# 03_-_LED7SEG.net
KiCad netlist of a schematic drawn in Altium Designer
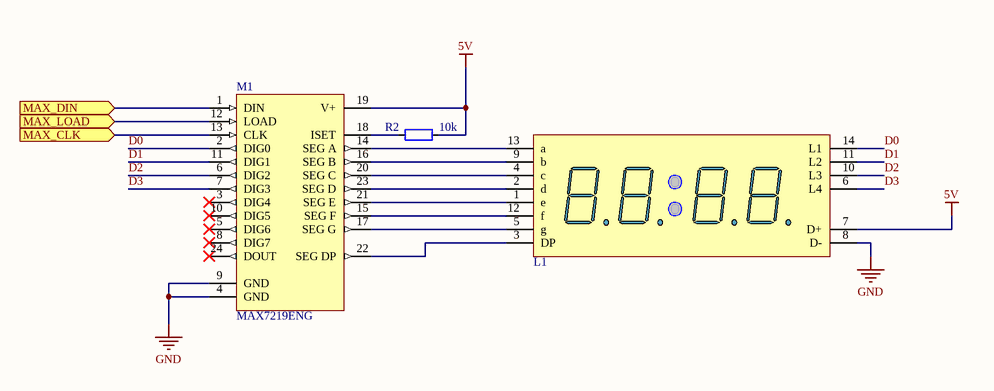
[diagram p0: [03] - LED7SEG.SchDoc]

(export (version "E")
  (design (tool "Eeschema 10.0.6"))
  (components
    (comp (ref "L1")
      (value "Led 7 Seg 4 digit - Anode")
      (footprint "LED7SEG-4-0.56-RG")
      (libsource (lib "My Library") (part "LED7SEG-4-RG"))
    )
    (comp (ref "M1")
      (value "MAX7219ENG")
      (footprint "DIP24/W0.3")
      (description "Serially Interfaced, 8-Digit LED Display Driver")
      (fields (field (name "PUBLISHER") "Altium Limited"))
      (libsource (lib "My Library") (part "MAX7219ENG"))
    )
    (comp (ref "R2")
      (value "10k")
      (footprint "RES-SMD-0805")
      (description "Resistor")
      (fields
        (field (name "MANUFACTURER") "Generic Components")
        (field (name "PUBLISHER") "Altium Hobart Technology Centre")
      )
      (libsource (lib "My Library") (part "Resistor - SMD"))
    )
  )
  (nets
    (net (code "1") (name "/D0") (class "Default")
      (node (ref "L1") (pin "14") (pinfunction "L1_14") (pintype "passive"))
      (node (ref "M1") (pin "2") (pinfunction "DIG0_2") (pintype "output"))
    )
    (net (code "2") (name "/D1") (class "Default")
      (node (ref "L1") (pin "11") (pinfunction "L2_11") (pintype "passive"))
      (node (ref "M1") (pin "11") (pinfunction "DIG1_11") (pintype "output"))
    )
    (net (code "3") (name "/D2") (class "Default")
      (node (ref "L1") (pin "10") (pinfunction "L3_10") (pintype "passive"))
      (node (ref "M1") (pin "6") (pinfunction "DIG2_6") (pintype "output"))
    )
    (net (code "4") (name "/D3") (class "Default")
      (node (ref "L1") (pin "6") (pinfunction "L4_6") (pintype "passive"))
      (node (ref "M1") (pin "7") (pinfunction "DIG3_7") (pintype "output"))
    )
    (net (code "5") (name "/MAX_CLK") (class "Default")
      (node (ref "M1") (pin "13") (pinfunction "CLK_13") (pintype "input"))
    )
    (net (code "6") (name "/MAX_DIN") (class "Default")
      (node (ref "M1") (pin "1") (pinfunction "DIN_1") (pintype "input"))
    )
    (net (code "7") (name "/MAX_LOAD") (class "Default")
      (node (ref "M1") (pin "12") (pinfunction "LOAD_12") (pintype "input"))
    )
    (net (code "8") (name "5V") (class "Default")
      (node (ref "L1") (pin "7") (pinfunction "D+_7") (pintype "passive"))
      (node (ref "M1") (pin "19") (pinfunction "V+_19") (pintype "power_in"))
      (node (ref "R2") (pin "2") (pinfunction "2_2") (pintype "passive"))
    )
    (net (code "9") (name "GND") (class "Default")
      (node (ref "L1") (pin "8") (pinfunction "D-_8") (pintype "passive"))
      (node (ref "M1") (pin "4") (pinfunction "GND_4") (pintype "power_in"))
      (node (ref "M1") (pin "9") (pinfunction "GND_9") (pintype "power_in"))
    )
    (net (code "10") (name "Net-(L1-DP)") (class "Default")
      (node (ref "L1") (pin "3") (pinfunction "DP_3") (pintype "passive"))
      (node (ref "M1") (pin "22") (pinfunction "SEG_DP_22") (pintype "output"))
    )
    (net (code "11") (name "Net-(L1-a)") (class "Default")
      (node (ref "L1") (pin "13") (pinfunction "a_13") (pintype "passive"))
      (node (ref "M1") (pin "14") (pinfunction "SEG_A_14") (pintype "output"))
    )
    (net (code "12") (name "Net-(L1-b)") (class "Default")
      (node (ref "L1") (pin "9") (pinfunction "b_9") (pintype "passive"))
      (node (ref "M1") (pin "16") (pinfunction "SEG_B_16") (pintype "output"))
    )
    (net (code "13") (name "Net-(L1-c)") (class "Default")
      (node (ref "L1") (pin "4") (pinfunction "c_4") (pintype "passive"))
      (node (ref "M1") (pin "20") (pinfunction "SEG_C_20") (pintype "output"))
    )
    (net (code "14") (name "Net-(L1-d)") (class "Default")
      (node (ref "L1") (pin "2") (pinfunction "d_2") (pintype "passive"))
      (node (ref "M1") (pin "23") (pinfunction "SEG_D_23") (pintype "output"))
    )
    (net (code "15") (name "Net-(L1-e)") (class "Default")
      (node (ref "L1") (pin "1") (pinfunction "e_1") (pintype "passive"))
      (node (ref "M1") (pin "21") (pinfunction "SEG_E_21") (pintype "output"))
    )
    (net (code "16") (name "Net-(L1-f)") (class "Default")
      (node (ref "L1") (pin "12") (pinfunction "f_12") (pintype "passive"))
      (node (ref "M1") (pin "15") (pinfunction "SEG_F_15") (pintype "output"))
    )
    (net (code "17") (name "Net-(L1-g)") (class "Default")
      (node (ref "L1") (pin "5") (pinfunction "g_5") (pintype "passive"))
      (node (ref "M1") (pin "17") (pinfunction "SEG_G_17") (pintype "output"))
    )
    (net (code "18") (name "Net-(M1-ISET)") (class "Default")
      (node (ref "M1") (pin "18") (pinfunction "ISET_18") (pintype "passive"))
      (node (ref "R2") (pin "1") (pinfunction "1_1") (pintype "passive"))
    )
    (net (code "19") (name "unconnected-(M1-DIG4-Pad3)") (class "Default")
      (node (ref "M1") (pin "3") (pinfunction "DIG4_3") (pintype "output+no_connect"))
    )
    (net (code "20") (name "unconnected-(M1-DIG5-Pad10)") (class "Default")
      (node (ref "M1") (pin "10") (pinfunction "DIG5_10") (pintype "output+no_connect"))
    )
    (net (code "21") (name "unconnected-(M1-DIG6-Pad5)") (class "Default")
      (node (ref "M1") (pin "5") (pinfunction "DIG6_5") (pintype "output+no_connect"))
    )
    (net (code "22") (name "unconnected-(M1-DIG7-Pad8)") (class "Default")
      (node (ref "M1") (pin "8") (pinfunction "DIG7_8") (pintype "output+no_connect"))
    )
    (net (code "23") (name "unconnected-(M1-DOUT-Pad24)") (class "Default")
      (node (ref "M1") (pin "24") (pinfunction "DOUT_24") (pintype "output+no_connect"))
    )
  )
)
